# eGAN-FET-module_Amplifier1.net
KiCad netlist of a schematic drawn in Altium Designer
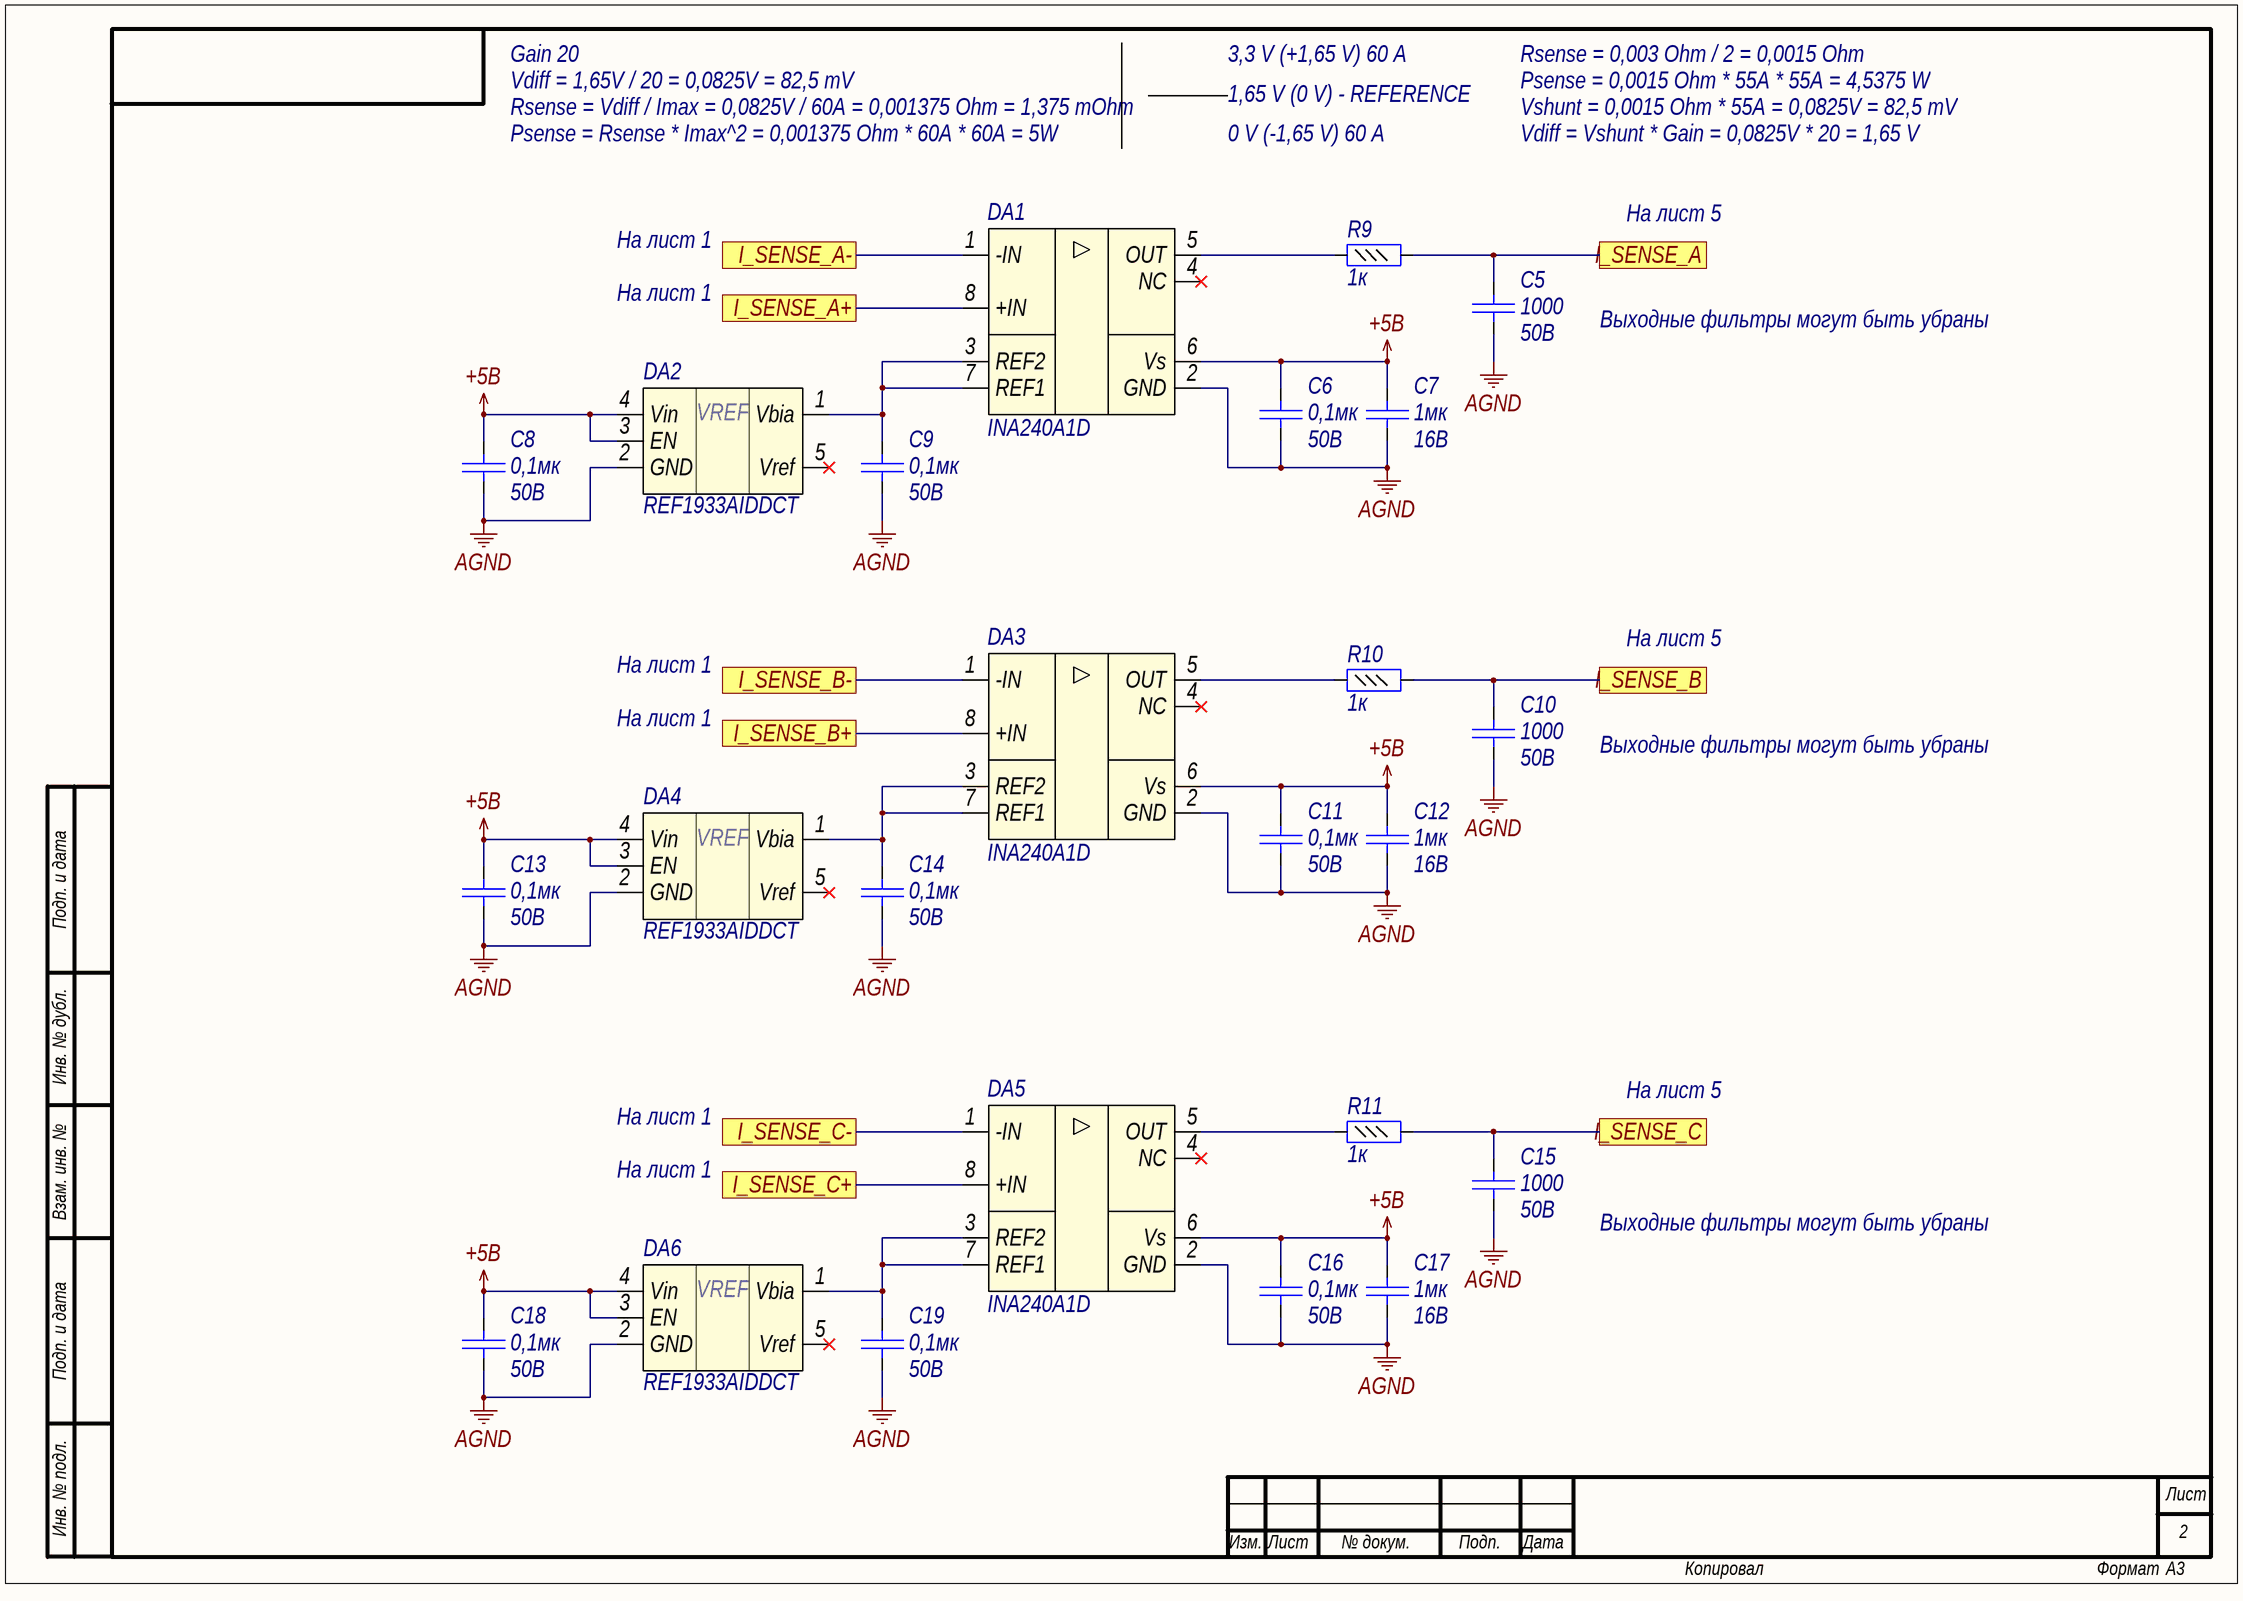
[diagram p0: eGAN-FET-module_Amplifier1.SchDoc]

(export (version "E")
  (design (tool "Eeschema 10.0.6"))
  (components
    (comp (ref "C5")
      (value "1000")
      (footprint "C0402")
      (description "Конденсатор")
      (fields
        (field (name "VOLTAGE") "50B")
        (field (name "PART NUMBER") "GRM1555C1H102J")
        (field (name "Comment") "Capacitor")
      )
      (libsource (lib "") (part "Capacitor_1"))
    )
    (comp (ref "C6")
      (value "0,1мк")
      (footprint "C0402")
      (description "Конденсатор")
      (fields
        (field (name "VOLTAGE") "50В")
        (field (name "PART NUMBER") "GRM155R71H104KE14D")
        (field (name "Comment") "Capacitor")
      )
      (libsource (lib "") (part "Capacitor_1"))
    )
    (comp (ref "C7")
      (value "1мк")
      (footprint "C0402")
      (description "Конденсатор")
      (fields (field (name "VOLTAGE") "16B") (field (name "PART NUMBER") "EMK105BJ105KV-F"))
      (libsource (lib "MOP44") (part "Capacitor"))
    )
    (comp (ref "C8")
      (value "0,1мк")
      (footprint "C0402")
      (description "Конденсатор")
      (fields
        (field (name "VOLTAGE") "50В")
        (field (name "PART NUMBER") "GRM155R71H104KE14D")
        (field (name "Comment") "Capacitor")
      )
      (libsource (lib "") (part "Capacitor_1"))
    )
    (comp (ref "C9")
      (value "0,1мк")
      (footprint "C0402")
      (description "Конденсатор")
      (fields
        (field (name "VOLTAGE") "50В")
        (field (name "PART NUMBER") "GRM155R71H104KE14D")
        (field (name "Comment") "Capacitor")
      )
      (libsource (lib "") (part "Capacitor_1"))
    )
    (comp (ref "C10")
      (value "1000")
      (footprint "C0402")
      (description "Конденсатор")
      (fields
        (field (name "VOLTAGE") "50B")
        (field (name "PART NUMBER") "GRM1555C1H102J")
        (field (name "Comment") "Capacitor")
      )
      (libsource (lib "") (part "Capacitor_1"))
    )
    (comp (ref "C11")
      (value "0,1мк")
      (footprint "C0402")
      (description "Конденсатор")
      (fields
        (field (name "VOLTAGE") "50В")
        (field (name "PART NUMBER") "GRM155R71H104KE14D")
        (field (name "Comment") "Capacitor")
      )
      (libsource (lib "") (part "Capacitor_1"))
    )
    (comp (ref "C12")
      (value "1мк")
      (footprint "C0402")
      (description "Конденсатор")
      (fields (field (name "VOLTAGE") "16B") (field (name "PART NUMBER") "EMK105BJ105KV-F"))
      (libsource (lib "MOP44") (part "Capacitor"))
    )
    (comp (ref "C13")
      (value "0,1мк")
      (footprint "C0402")
      (description "Конденсатор")
      (fields
        (field (name "VOLTAGE") "50В")
        (field (name "PART NUMBER") "GRM155R71H104KE14D")
        (field (name "Comment") "Capacitor")
      )
      (libsource (lib "") (part "Capacitor_1"))
    )
    (comp (ref "C14")
      (value "0,1мк")
      (footprint "C0402")
      (description "Конденсатор")
      (fields
        (field (name "VOLTAGE") "50В")
        (field (name "PART NUMBER") "GRM155R71H104KE14D")
        (field (name "Comment") "Capacitor")
      )
      (libsource (lib "") (part "Capacitor_1"))
    )
    (comp (ref "C15")
      (value "1000")
      (footprint "C0402")
      (description "Конденсатор")
      (fields
        (field (name "VOLTAGE") "50B")
        (field (name "PART NUMBER") "GRM1555C1H102J")
        (field (name "Comment") "Capacitor")
      )
      (libsource (lib "") (part "Capacitor_1"))
    )
    (comp (ref "C16")
      (value "0,1мк")
      (footprint "C0402")
      (description "Конденсатор")
      (fields
        (field (name "VOLTAGE") "50В")
        (field (name "PART NUMBER") "GRM155R71H104KE14D")
        (field (name "Comment") "Capacitor")
      )
      (libsource (lib "") (part "Capacitor_1"))
    )
    (comp (ref "C17")
      (value "1мк")
      (footprint "C0402")
      (description "Конденсатор")
      (fields (field (name "VOLTAGE") "16B") (field (name "PART NUMBER") "EMK105BJ105KV-F"))
      (libsource (lib "MOP44") (part "Capacitor"))
    )
    (comp (ref "C18")
      (value "0,1мк")
      (footprint "C0402")
      (description "Конденсатор")
      (fields
        (field (name "VOLTAGE") "50В")
        (field (name "PART NUMBER") "GRM155R71H104KE14D")
        (field (name "Comment") "Capacitor")
      )
      (libsource (lib "") (part "Capacitor_1"))
    )
    (comp (ref "C19")
      (value "0,1мк")
      (footprint "C0402")
      (description "Конденсатор")
      (fields
        (field (name "VOLTAGE") "50В")
        (field (name "PART NUMBER") "GRM155R71H104KE14D")
        (field (name "Comment") "Capacitor")
      )
      (libsource (lib "") (part "Capacitor_1"))
    )
    (comp (ref "DA1")
      (value "INA240A1D")
      (footprint "SO8")
      (description "–4-V to 80-V, Bidirectional, Ultra-Precise Current Sense Amplifier With\r\nEnhanced PWM Rejection")
      (libsource (lib "MOP44") (part "INA240"))
    )
    (comp (ref "DA2")
      (value "REF1933AIDDCT")
      (footprint "SOT23-5")
      (description ", Dual-Output, VREF and VREF / 2 Voltage References")
      (fields (field (name "MANUFACTURER") "Texas Instruments"))
      (libsource (lib "MOP44") (part "REF19xx"))
    )
    (comp (ref "DA3")
      (value "INA240A1D")
      (footprint "SO8")
      (description "–4-V to 80-V, Bidirectional, Ultra-Precise Current Sense Amplifier With\r\nEnhanced PWM Rejection")
      (libsource (lib "MOP44") (part "INA240"))
    )
    (comp (ref "DA4")
      (value "REF1933AIDDCT")
      (footprint "SOT23-5")
      (description ", Dual-Output, VREF and VREF / 2 Voltage References")
      (fields (field (name "MANUFACTURER") "Texas Instruments"))
      (libsource (lib "MOP44") (part "REF19xx"))
    )
    (comp (ref "DA5")
      (value "INA240A1D")
      (footprint "SO8")
      (description "–4-V to 80-V, Bidirectional, Ultra-Precise Current Sense Amplifier With\r\nEnhanced PWM Rejection")
      (libsource (lib "MOP44") (part "INA240"))
    )
    (comp (ref "DA6")
      (value "REF1933AIDDCT")
      (footprint "SOT23-5")
      (description ", Dual-Output, VREF and VREF / 2 Voltage References")
      (fields (field (name "MANUFACTURER") "Texas Instruments"))
      (libsource (lib "MOP44") (part "REF19xx"))
    )
    (comp (ref "R9")
      (value "1к")
      (footprint "R0402")
      (description "Резистор")
      (fields (field (name "PART NUMBER") "RC0402FR-071KL") (field (name "POWER") "0,062Вт"))
      (libsource (lib "MOP44") (part "Resistor_0,062Вт"))
    )
    (comp (ref "R10")
      (value "1к")
      (footprint "R0402")
      (description "Резистор")
      (fields (field (name "PART NUMBER") "RC0402FR-071KL") (field (name "POWER") "0,062Вт"))
      (libsource (lib "MOP44") (part "Resistor_0,062Вт"))
    )
    (comp (ref "R11")
      (value "1к")
      (footprint "R0402")
      (description "Резистор")
      (fields (field (name "PART NUMBER") "RC0402FR-071KL") (field (name "POWER") "0,062Вт"))
      (libsource (lib "MOP44") (part "Resistor_0,062Вт"))
    )
  )
  (nets
    (net (code "1") (name "+5B") (class "Default")
      (node (ref "C11") (pin "2") (pinfunction "2_2") (pintype "passive"))
      (node (ref "C12") (pin "2") (pinfunction "2_2") (pintype "passive"))
      (node (ref "C13") (pin "2") (pinfunction "2_2") (pintype "passive"))
      (node (ref "C16") (pin "2") (pinfunction "2_2") (pintype "passive"))
      (node (ref "C17") (pin "2") (pinfunction "2_2") (pintype "passive"))
      (node (ref "C18") (pin "2") (pinfunction "2_2") (pintype "passive"))
      (node (ref "C6") (pin "2") (pinfunction "2_2") (pintype "passive"))
      (node (ref "C7") (pin "2") (pinfunction "2_2") (pintype "passive"))
      (node (ref "C8") (pin "2") (pinfunction "2_2") (pintype "passive"))
      (node (ref "DA1") (pin "6") (pinfunction "Vs_6") (pintype "passive"))
      (node (ref "DA2") (pin "3") (pinfunction "EN_3") (pintype "passive"))
      (node (ref "DA2") (pin "4") (pinfunction "Vin_4") (pintype "passive"))
      (node (ref "DA3") (pin "6") (pinfunction "Vs_6") (pintype "passive"))
      (node (ref "DA4") (pin "3") (pinfunction "EN_3") (pintype "passive"))
      (node (ref "DA4") (pin "4") (pinfunction "Vin_4") (pintype "passive"))
      (node (ref "DA5") (pin "6") (pinfunction "Vs_6") (pintype "passive"))
      (node (ref "DA6") (pin "3") (pinfunction "EN_3") (pintype "passive"))
      (node (ref "DA6") (pin "4") (pinfunction "Vin_4") (pintype "passive"))
    )
    (net (code "2") (name "/I_SENSE_A") (class "Default")
      (node (ref "C5") (pin "2") (pinfunction "2_2") (pintype "passive"))
      (node (ref "R9") (pin "2") (pinfunction "2_2") (pintype "passive"))
    )
    (net (code "3") (name "/I_SENSE_A+") (class "Default")
      (node (ref "DA1") (pin "8") (pinfunction "+IN_8") (pintype "passive"))
    )
    (net (code "4") (name "/I_SENSE_A-") (class "Default")
      (node (ref "DA1") (pin "1") (pinfunction "-IN_1") (pintype "passive"))
    )
    (net (code "5") (name "/I_SENSE_B") (class "Default")
      (node (ref "C10") (pin "2") (pinfunction "2_2") (pintype "passive"))
      (node (ref "R10") (pin "2") (pinfunction "2_2") (pintype "passive"))
    )
    (net (code "6") (name "/I_SENSE_B+") (class "Default")
      (node (ref "DA3") (pin "8") (pinfunction "+IN_8") (pintype "passive"))
    )
    (net (code "7") (name "/I_SENSE_B-") (class "Default")
      (node (ref "DA3") (pin "1") (pinfunction "-IN_1") (pintype "passive"))
    )
    (net (code "8") (name "/I_SENSE_C") (class "Default")
      (node (ref "C15") (pin "2") (pinfunction "2_2") (pintype "passive"))
      (node (ref "R11") (pin "2") (pinfunction "2_2") (pintype "passive"))
    )
    (net (code "9") (name "/I_SENSE_C+") (class "Default")
      (node (ref "DA5") (pin "8") (pinfunction "+IN_8") (pintype "passive"))
    )
    (net (code "10") (name "/I_SENSE_C-") (class "Default")
      (node (ref "DA5") (pin "1") (pinfunction "-IN_1") (pintype "passive"))
    )
    (net (code "11") (name "AGND") (class "Default")
      (node (ref "C10") (pin "1") (pinfunction "1_1") (pintype "passive"))
      (node (ref "C11") (pin "1") (pinfunction "1_1") (pintype "passive"))
      (node (ref "C12") (pin "1") (pinfunction "1_1") (pintype "passive"))
      (node (ref "C13") (pin "1") (pinfunction "1_1") (pintype "passive"))
      (node (ref "C14") (pin "1") (pinfunction "1_1") (pintype "passive"))
      (node (ref "C15") (pin "1") (pinfunction "1_1") (pintype "passive"))
      (node (ref "C16") (pin "1") (pinfunction "1_1") (pintype "passive"))
      (node (ref "C17") (pin "1") (pinfunction "1_1") (pintype "passive"))
      (node (ref "C18") (pin "1") (pinfunction "1_1") (pintype "passive"))
      (node (ref "C19") (pin "1") (pinfunction "1_1") (pintype "passive"))
      (node (ref "C5") (pin "1") (pinfunction "1_1") (pintype "passive"))
      (node (ref "C6") (pin "1") (pinfunction "1_1") (pintype "passive"))
      (node (ref "C7") (pin "1") (pinfunction "1_1") (pintype "passive"))
      (node (ref "C8") (pin "1") (pinfunction "1_1") (pintype "passive"))
      (node (ref "C9") (pin "1") (pinfunction "1_1") (pintype "passive"))
      (node (ref "DA1") (pin "2") (pinfunction "GND_2") (pintype "passive"))
      (node (ref "DA2") (pin "2") (pinfunction "GND_2") (pintype "passive"))
      (node (ref "DA3") (pin "2") (pinfunction "GND_2") (pintype "passive"))
      (node (ref "DA4") (pin "2") (pinfunction "GND_2") (pintype "passive"))
      (node (ref "DA5") (pin "2") (pinfunction "GND_2") (pintype "passive"))
      (node (ref "DA6") (pin "2") (pinfunction "GND_2") (pintype "passive"))
    )
    (net (code "12") (name "Net-(DA1-OUT)") (class "Default")
      (node (ref "DA1") (pin "5") (pinfunction "OUT_5") (pintype "passive"))
      (node (ref "R9") (pin "1") (pinfunction "1_1") (pintype "passive"))
    )
    (net (code "13") (name "Net-(DA1-REF1)") (class "Default")
      (node (ref "C9") (pin "2") (pinfunction "2_2") (pintype "passive"))
      (node (ref "DA1") (pin "3") (pinfunction "REF2_3") (pintype "passive"))
      (node (ref "DA1") (pin "7") (pinfunction "REF1_7") (pintype "passive"))
      (node (ref "DA2") (pin "1") (pinfunction "Vbia_1") (pintype "passive"))
    )
    (net (code "14") (name "Net-(DA3-OUT)") (class "Default")
      (node (ref "DA3") (pin "5") (pinfunction "OUT_5") (pintype "passive"))
      (node (ref "R10") (pin "1") (pinfunction "1_1") (pintype "passive"))
    )
    (net (code "15") (name "Net-(DA3-REF1)") (class "Default")
      (node (ref "C14") (pin "2") (pinfunction "2_2") (pintype "passive"))
      (node (ref "DA3") (pin "3") (pinfunction "REF2_3") (pintype "passive"))
      (node (ref "DA3") (pin "7") (pinfunction "REF1_7") (pintype "passive"))
      (node (ref "DA4") (pin "1") (pinfunction "Vbia_1") (pintype "passive"))
    )
    (net (code "16") (name "Net-(DA5-OUT)") (class "Default")
      (node (ref "DA5") (pin "5") (pinfunction "OUT_5") (pintype "passive"))
      (node (ref "R11") (pin "1") (pinfunction "1_1") (pintype "passive"))
    )
    (net (code "17") (name "Net-(DA5-REF1)") (class "Default")
      (node (ref "C19") (pin "2") (pinfunction "2_2") (pintype "passive"))
      (node (ref "DA5") (pin "3") (pinfunction "REF2_3") (pintype "passive"))
      (node (ref "DA5") (pin "7") (pinfunction "REF1_7") (pintype "passive"))
      (node (ref "DA6") (pin "1") (pinfunction "Vbia_1") (pintype "passive"))
    )
    (net (code "18") (name "unconnected-(DA1-NC-Pad4)") (class "Default")
      (node (ref "DA1") (pin "4") (pinfunction "NC_4") (pintype "passive+no_connect"))
    )
    (net (code "19") (name "unconnected-(DA2-Vref-Pad5)") (class "Default")
      (node (ref "DA2") (pin "5") (pinfunction "Vref_5") (pintype "passive+no_connect"))
    )
    (net (code "20") (name "unconnected-(DA3-NC-Pad4)") (class "Default")
      (node (ref "DA3") (pin "4") (pinfunction "NC_4") (pintype "passive+no_connect"))
    )
    (net (code "21") (name "unconnected-(DA4-Vref-Pad5)") (class "Default")
      (node (ref "DA4") (pin "5") (pinfunction "Vref_5") (pintype "passive+no_connect"))
    )
    (net (code "22") (name "unconnected-(DA5-NC-Pad4)") (class "Default")
      (node (ref "DA5") (pin "4") (pinfunction "NC_4") (pintype "passive+no_connect"))
    )
    (net (code "23") (name "unconnected-(DA6-Vref-Pad5)") (class "Default")
      (node (ref "DA6") (pin "5") (pinfunction "Vref_5") (pintype "passive+no_connect"))
    )
  )
)
